# STM32_Schematic.net
KiCad netlist of a schematic drawn in Altium Designer
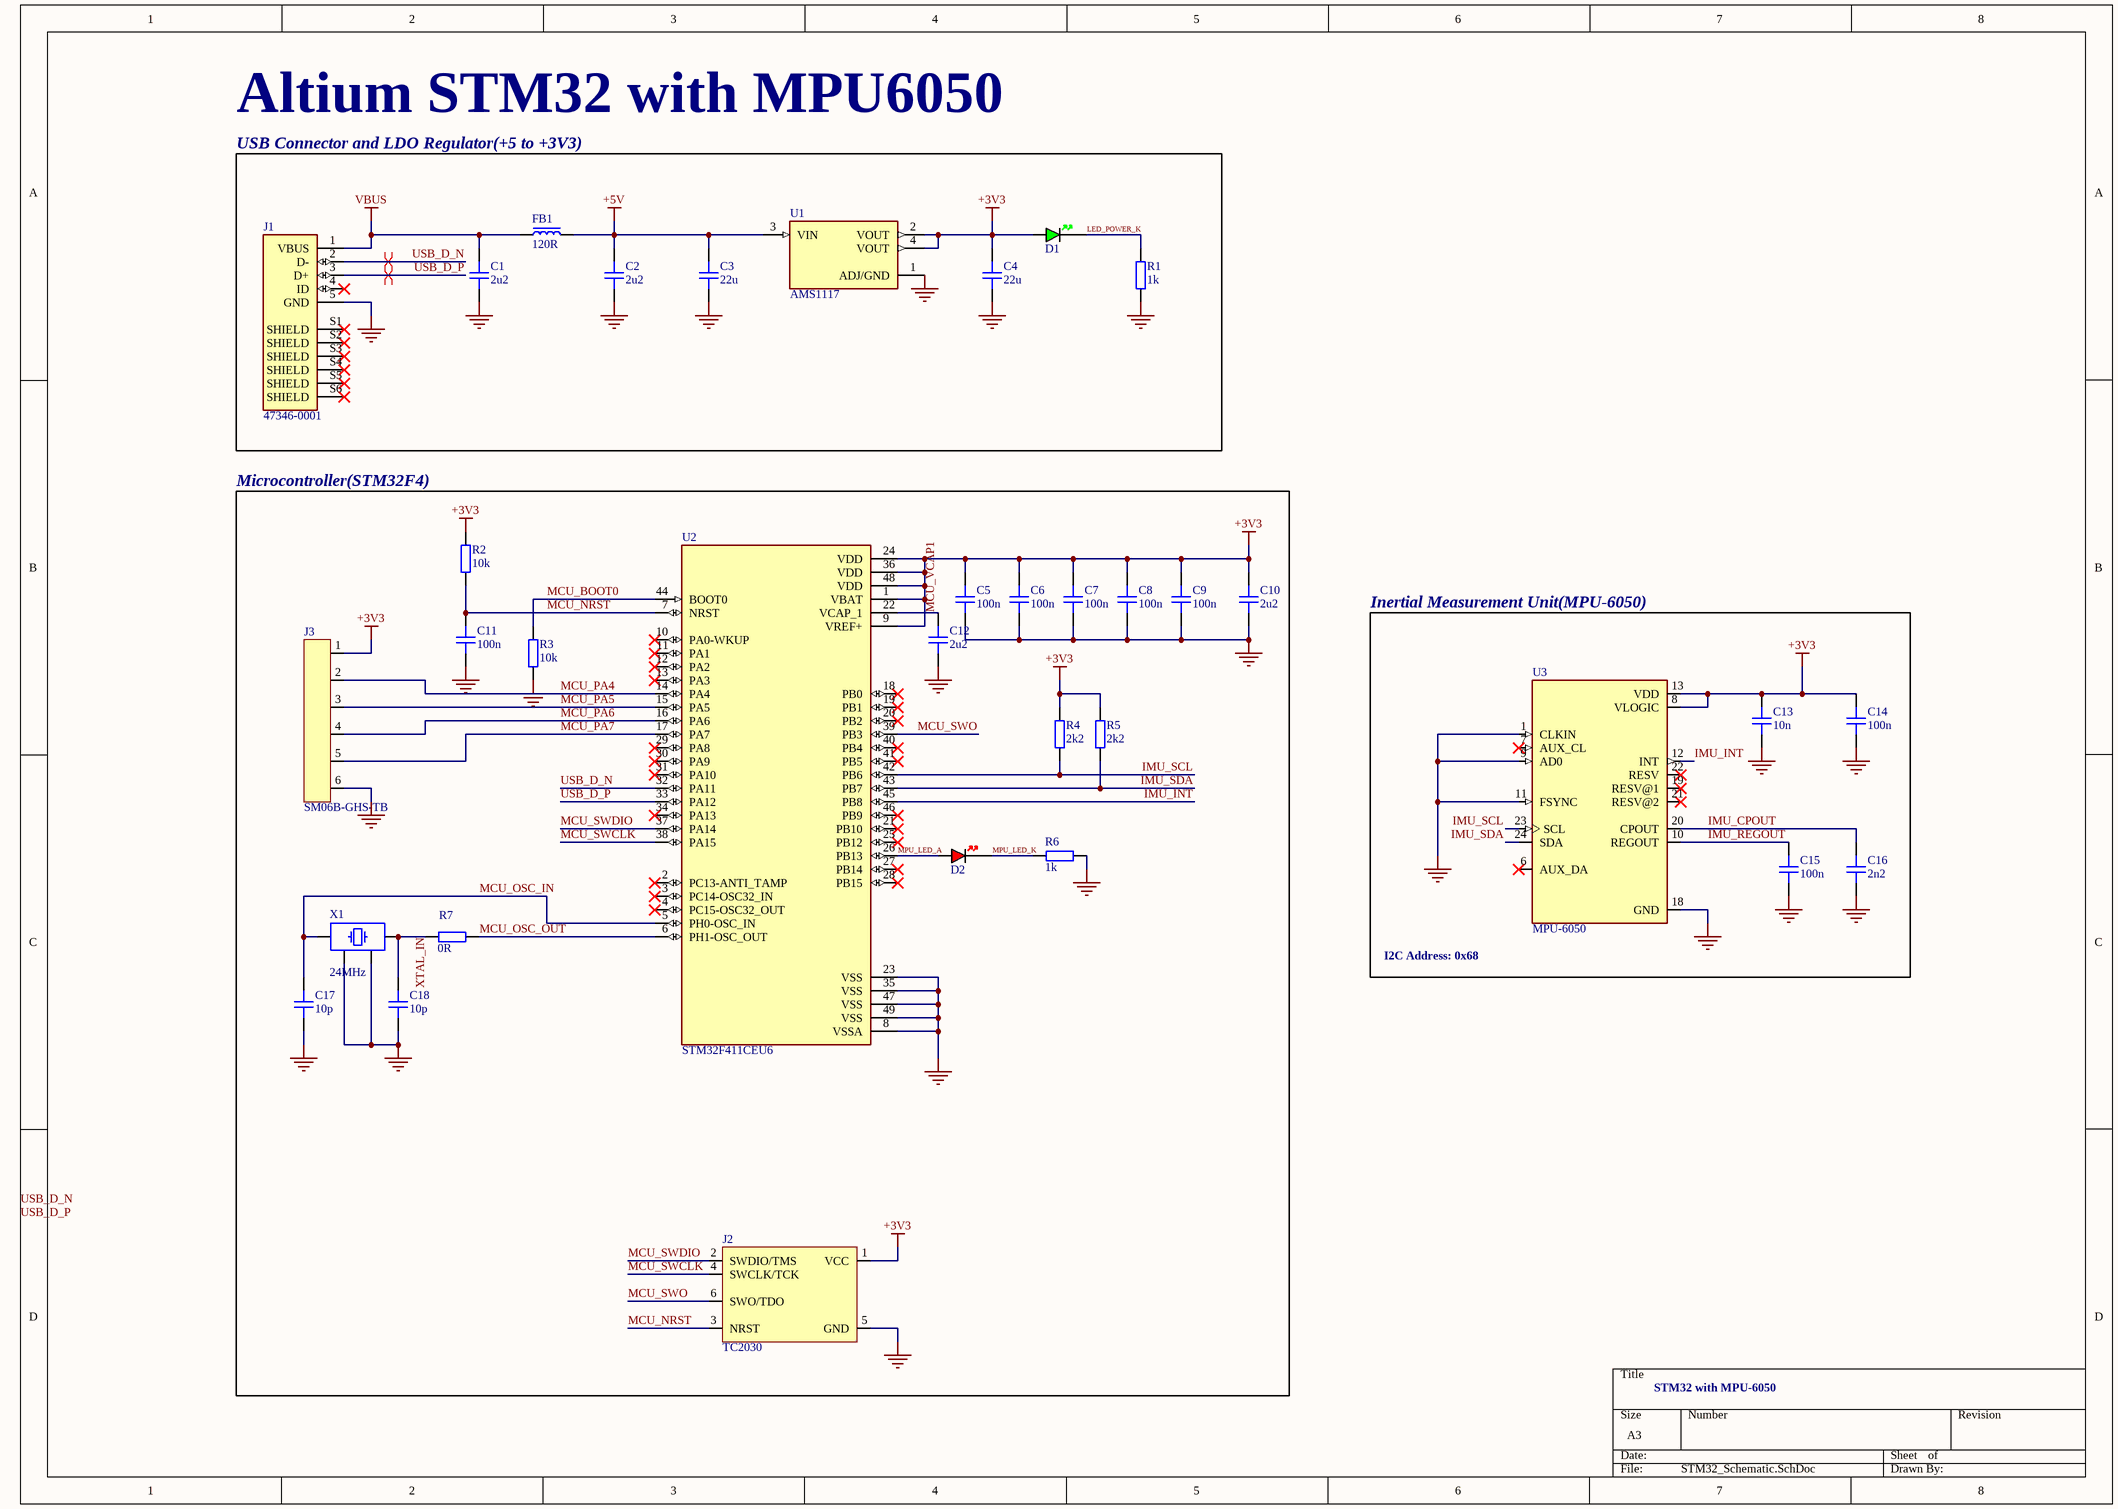
[diagram p0: STM32_Schematic.SchDoc]

(export (version "E")
  (design (tool "Eeschema 10.0.6"))
  (components
    (comp (ref "C1")
      (value "2u2")
      (footprint "CAP_0603")
      (description "Capacitor SMD 0603 16V")
      (libsource (lib "Schematic-Lib-PhilsLab") (part "CAP_0603_16V"))
    )
    (comp (ref "C2")
      (value "2u2")
      (footprint "CAP_0603")
      (description "Capacitor SMD 0603 16V")
      (libsource (lib "Schematic-Lib-PhilsLab") (part "CAP_0603_16V"))
    )
    (comp (ref "C3")
      (value "22u")
      (footprint "CAP_0805")
      (description "Capacitor SMD 0805 16V")
      (libsource (lib "Schematic-Lib-PhilsLab") (part "CAP_0805_16V"))
    )
    (comp (ref "C4")
      (value "22u")
      (footprint "CAP_0805")
      (description "Capacitor SMD 0805 16V")
      (libsource (lib "Schematic-Lib-PhilsLab") (part "CAP_0805_16V"))
    )
    (comp (ref "C5")
      (value "100n")
      (footprint "CAP_0402")
      (description "Capacitor SMD 0402 16V")
      (libsource (lib "Schematic-Lib-PhilsLab") (part "CAP_0402_16V"))
    )
    (comp (ref "C6")
      (value "100n")
      (footprint "CAP_0402")
      (description "Capacitor SMD 0402 16V")
      (libsource (lib "Schematic-Lib-PhilsLab") (part "CAP_0402_16V"))
    )
    (comp (ref "C7")
      (value "100n")
      (footprint "CAP_0402")
      (description "Capacitor SMD 0402 16V")
      (libsource (lib "Schematic-Lib-PhilsLab") (part "CAP_0402_16V"))
    )
    (comp (ref "C8")
      (value "100n")
      (footprint "CAP_0402")
      (description "Capacitor SMD 0402 16V")
      (libsource (lib "Schematic-Lib-PhilsLab") (part "CAP_0402_16V"))
    )
    (comp (ref "C9")
      (value "100n")
      (footprint "CAP_0402")
      (description "Capacitor SMD 0402 16V")
      (libsource (lib "Schematic-Lib-PhilsLab") (part "CAP_0402_16V"))
    )
    (comp (ref "C10")
      (value "2u2")
      (footprint "CAP_0603")
      (description "Capacitor SMD 0603 16V")
      (libsource (lib "Schematic-Lib-PhilsLab") (part "CAP_0603_16V"))
    )
    (comp (ref "C11")
      (value "100n")
      (footprint "CAP_0402")
      (description "Capacitor SMD 0402 16V")
      (libsource (lib "Schematic-Lib-PhilsLab") (part "CAP_0402_16V"))
    )
    (comp (ref "C12")
      (value "2u2")
      (footprint "CAP_0603")
      (description "Capacitor SMD 0603 16V")
      (libsource (lib "Schematic-Lib-PhilsLab") (part "CAP_0603_16V"))
    )
    (comp (ref "C13")
      (value "10n")
      (footprint "CAP_0402")
      (description "Capacitor SMD 0402 16V")
      (libsource (lib "Schematic-Lib-PhilsLab") (part "CAP_0402_16V"))
    )
    (comp (ref "C14")
      (value "100n")
      (footprint "CAP_0402")
      (description "Capacitor SMD 0402 16V")
      (libsource (lib "Schematic-Lib-PhilsLab") (part "CAP_0402_16V"))
    )
    (comp (ref "C15")
      (value "100n")
      (footprint "CAP_0402")
      (description "Capacitor SMD 0402 16V")
      (libsource (lib "Schematic-Lib-PhilsLab") (part "CAP_0402_16V"))
    )
    (comp (ref "C16")
      (value "2n2")
      (footprint "CAP_0402")
      (description "Capacitor SMD 0402 16V")
      (libsource (lib "Schematic-Lib-PhilsLab") (part "CAP_0402_16V"))
    )
    (comp (ref "C17")
      (value "10p")
      (footprint "CAP_0402")
      (description "Capacitor SMD 0402 16V")
      (libsource (lib "Schematic-Lib-PhilsLab") (part "CAP_0402_16V"))
    )
    (comp (ref "C18")
      (value "10p")
      (footprint "CAP_0402")
      (description "Capacitor SMD 0402 16V")
      (libsource (lib "Schematic-Lib-PhilsLab") (part "CAP_0402_16V"))
    )
    (comp (ref "D1")
      (value "GREEN")
      (footprint "LED_0402_GREEN")
      (description "LED 0402 GREEN SMD")
      (libsource (lib "Schematic-Lib-PhilsLab") (part "LED_0402_GREEN"))
    )
    (comp (ref "D2")
      (value "RED")
      (footprint "LED_0402_RED")
      (description "LED 0402 RED SMD")
      (libsource (lib "Schematic-Lib-PhilsLab") (part "LED_0402_RED"))
    )
    (comp (ref "FB1")
      (value "120R")
      (footprint "FB_0603")
      (description "Ferrite Bead SMD 0603")
      (libsource (lib "Schematic-Lib-PhilsLab") (part "FB_0603"))
    )
    (comp (ref "J1")
      (value "47346-0001")
      (footprint "MOLEX_47346-0001")
      (description "USB - micro B USB 2.0 Receptacle Connector 5 Position Surface Mount, Right Angle")
      (fields (field (name "MF") "Molex"))
      (libsource (lib "47346-0001") (part "47346-0001"))
    )
    (comp (ref "J2")
      (value "TC2030")
      (footprint "TC2030-FP")
      (description "Tag-Connect No-Solder SWD Debug Connector DO NOT PLACE")
      (fields (field (name "MANUFACTURER") "Tag-Connect"))
      (libsource (lib "Schematic-Lib-PhilsLab") (part "TC2030"))
    )
    (comp (ref "J3")
      (value "SM06B-GHS-TB")
      (footprint "SM06B-GHS-TB")
      (description "Header Connector 6 Position 1.25MM Pitch SMD Horizontal JST GH")
      (fields (field (name "MANUFACTURER") "JST"))
      (libsource (lib "Schematic-Lib-PhilsLab") (part "SM06B-GHS-TB"))
    )
    (comp (ref "R1")
      (value "1k")
      (footprint "RES_0402")
      (description "Resistor SMD 0402")
      (libsource (lib "Schematic-Lib-PhilsLab") (part "RES_0402"))
    )
    (comp (ref "R2")
      (value "10k")
      (footprint "RES_0402")
      (description "Resistor SMD 0402")
      (libsource (lib "Schematic-Lib-PhilsLab") (part "RES_0402"))
    )
    (comp (ref "R3")
      (value "10k")
      (footprint "RES_0402")
      (description "Resistor SMD 0402")
      (libsource (lib "Schematic-Lib-PhilsLab") (part "RES_0402"))
    )
    (comp (ref "R4")
      (value "2k2")
      (footprint "RES_0402")
      (description "Resistor SMD 0402")
      (libsource (lib "Schematic-Lib-PhilsLab") (part "RES_0402"))
    )
    (comp (ref "R5")
      (value "2k2")
      (footprint "RES_0402")
      (description "Resistor SMD 0402")
      (libsource (lib "Schematic-Lib-PhilsLab") (part "RES_0402"))
    )
    (comp (ref "R6")
      (value "1k")
      (footprint "RES_0402")
      (description "Resistor SMD 0402")
      (libsource (lib "Schematic-Lib-PhilsLab") (part "RES_0402"))
    )
    (comp (ref "R7")
      (value "0R")
      (footprint "RES_0402")
      (description "Resistor SMD 0402")
      (libsource (lib "Schematic-Lib-PhilsLab") (part "RES_0402"))
    )
    (comp (ref "U1")
      (value "AMS1117")
      (footprint "SOT229P700X180-4N")
      (description "1A LOW DROPOUT VOLTAGE REGULATOR SOT-223")
      (fields (field (name "MF") "Advanced Monolithic Systems"))
      (libsource (lib "AMS1117") (part "AMS1117"))
    )
    (comp (ref "U2")
      (value "STM32F411CEU6")
      (footprint "QFN50P700X700X60-49N:QFN50P700X700X60-49N")
      (libsource (lib "STM32F411CEU6") (part "STM32F411CEU6"))
    )
    (comp (ref "U3")
      (value "MPU-6050")
      (footprint "QFN50P400X400X95-24N")
      (description "MPU-6050 series Accelerometer, Gyroscope, 3 Axis Sensor Evaluation Board")
      (fields (field (name "MF") "TDK InvenSense"))
      (libsource (lib "MPU-6050") (part "MPU-6050"))
    )
    (comp (ref "X1")
      (value "24MHz")
      (footprint "XTAL_3225")
      (description "Crystal SMD 24MHz 10PPM 7pF 3225")
      (fields
        (field (name "MANUFACTURER") "Epson")
        (field (name "MANUFACTURER PART NUMBER") "TSX-3225 24.0000MF15X-AC")
      )
      (libsource (lib "Schematic-Lib-PhilsLab") (part "TSX-3225_24.0000MF15X-AC"))
    )
  )
  (nets
    (net (code "1") (name "+3V3") (class "Default")
      (node (ref "C10") (pin "1") (pinfunction "1_1") (pintype "passive"))
      (node (ref "C13") (pin "1") (pinfunction "1_1") (pintype "passive"))
      (node (ref "C14") (pin "1") (pinfunction "1_1") (pintype "passive"))
      (node (ref "C4") (pin "2") (pinfunction "2_2") (pintype "passive"))
      (node (ref "C5") (pin "2") (pinfunction "2_2") (pintype "passive"))
      (node (ref "C6") (pin "2") (pinfunction "2_2") (pintype "passive"))
      (node (ref "C7") (pin "2") (pinfunction "2_2") (pintype "passive"))
      (node (ref "C8") (pin "2") (pinfunction "2_2") (pintype "passive"))
      (node (ref "C9") (pin "1") (pinfunction "1_1") (pintype "passive"))
      (node (ref "D1") (pin "A") (pinfunction "A_A") (pintype "passive"))
      (node (ref "J2") (pin "1") (pinfunction "VCC_1") (pintype "passive"))
      (node (ref "J3") (pin "1") (pinfunction "1_1") (pintype "passive"))
      (node (ref "R2") (pin "2") (pinfunction "2_2") (pintype "passive"))
      (node (ref "R4") (pin "2") (pinfunction "2_2") (pintype "passive"))
      (node (ref "R5") (pin "2") (pinfunction "2_2") (pintype "passive"))
      (node (ref "U1") (pin "2") (pinfunction "VOUT_2") (pintype "output"))
      (node (ref "U1") (pin "4") (pinfunction "VOUT_4") (pintype "output"))
      (node (ref "U2") (pin "1") (pinfunction "VBAT_1") (pintype "power_in"))
      (node (ref "U2") (pin "24") (pinfunction "VDD_24") (pintype "power_in"))
      (node (ref "U2") (pin "36") (pinfunction "VDD_36") (pintype "power_in"))
      (node (ref "U2") (pin "48") (pinfunction "VDD_48") (pintype "power_in"))
      (node (ref "U2") (pin "9") (pinfunction "VREF+_9") (pintype "power_in"))
      (node (ref "U3") (pin "13") (pinfunction "VDD_13") (pintype "power_in"))
      (node (ref "U3") (pin "8") (pinfunction "VLOGIC_8") (pintype "power_in"))
    )
    (net (code "2") (name "+5V") (class "Default")
      (node (ref "C2") (pin "2") (pinfunction "2_2") (pintype "passive"))
      (node (ref "C3") (pin "2") (pinfunction "2_2") (pintype "passive"))
      (node (ref "FB1") (pin "2") (pinfunction "2_2") (pintype "passive"))
      (node (ref "U1") (pin "3") (pinfunction "VIN_3") (pintype "input"))
    )
    (net (code "3") (name "/IMU_CPOUT") (class "Default")
      (node (ref "C16") (pin "1") (pinfunction "1_1") (pintype "passive"))
      (node (ref "U3") (pin "20") (pinfunction "CPOUT_20") (pintype "passive"))
    )
    (net (code "4") (name "/IMU_INT") (class "Default")
      (node (ref "U2") (pin "45") (pinfunction "PB8_45") (pintype "bidirectional"))
      (node (ref "U3") (pin "12") (pinfunction "INT_12") (pintype "output"))
    )
    (net (code "5") (name "/IMU_REGOUT") (class "Default")
      (node (ref "C15") (pin "1") (pinfunction "1_1") (pintype "passive"))
      (node (ref "U3") (pin "10") (pinfunction "REGOUT_10") (pintype "passive"))
    )
    (net (code "6") (name "/IMU_SCL") (class "Default")
      (node (ref "R4") (pin "1") (pinfunction "1_1") (pintype "passive"))
      (node (ref "U2") (pin "42") (pinfunction "PB6_42") (pintype "bidirectional"))
      (node (ref "U3") (pin "23") (pinfunction "SCL_23") (pintype "input"))
    )
    (net (code "7") (name "/IMU_SDA") (class "Default")
      (node (ref "R5") (pin "1") (pinfunction "1_1") (pintype "passive"))
      (node (ref "U2") (pin "43") (pinfunction "PB7_43") (pintype "bidirectional"))
      (node (ref "U3") (pin "24") (pinfunction "SDA_24") (pintype "bidirectional"))
    )
    (net (code "8") (name "/LED_POWER_K") (class "Default")
      (node (ref "D1") (pin "K") (pinfunction "K_K") (pintype "passive"))
      (node (ref "R1") (pin "2") (pinfunction "2_2") (pintype "passive"))
    )
    (net (code "9") (name "/MCU_BOOT0") (class "Default")
      (node (ref "R3") (pin "2") (pinfunction "2_2") (pintype "passive"))
      (node (ref "U2") (pin "44") (pinfunction "BOOT0_44") (pintype "input"))
    )
    (net (code "10") (name "/MCU_NRST") (class "Default")
      (node (ref "C11") (pin "2") (pinfunction "2_2") (pintype "passive"))
      (node (ref "J2") (pin "3") (pinfunction "NRST_3") (pintype "passive"))
      (node (ref "R2") (pin "1") (pinfunction "1_1") (pintype "passive"))
      (node (ref "U2") (pin "7") (pinfunction "NRST_7") (pintype "bidirectional"))
    )
    (net (code "11") (name "/MCU_OSC_IN") (class "Default")
      (node (ref "C17") (pin "2") (pinfunction "2_2") (pintype "passive"))
      (node (ref "U2") (pin "5") (pinfunction "PH0-OSC_IN_5") (pintype "bidirectional"))
      (node (ref "X1") (pin "1") (pinfunction "1_1") (pintype "passive"))
    )
    (net (code "12") (name "/MCU_OSC_OUT") (class "Default")
      (node (ref "R7") (pin "2") (pinfunction "2_2") (pintype "passive"))
      (node (ref "U2") (pin "6") (pinfunction "PH1-OSC_OUT_6") (pintype "bidirectional"))
    )
    (net (code "13") (name "/MCU_PA4") (class "Default")
      (node (ref "J3") (pin "2") (pinfunction "2_2") (pintype "passive"))
      (node (ref "U2") (pin "14") (pinfunction "PA4_14") (pintype "bidirectional"))
    )
    (net (code "14") (name "/MCU_PA5") (class "Default")
      (node (ref "J3") (pin "3") (pinfunction "3_3") (pintype "passive"))
      (node (ref "U2") (pin "15") (pinfunction "PA5_15") (pintype "bidirectional"))
    )
    (net (code "15") (name "/MCU_PA6") (class "Default")
      (node (ref "J3") (pin "4") (pinfunction "4_4") (pintype "passive"))
      (node (ref "U2") (pin "16") (pinfunction "PA6_16") (pintype "bidirectional"))
    )
    (net (code "16") (name "/MCU_PA7") (class "Default")
      (node (ref "J3") (pin "5") (pinfunction "5_5") (pintype "passive"))
      (node (ref "U2") (pin "17") (pinfunction "PA7_17") (pintype "bidirectional"))
    )
    (net (code "17") (name "/MCU_SWCLK") (class "Default")
      (node (ref "J2") (pin "4") (pinfunction "SWCLK/TCK_4") (pintype "passive"))
      (node (ref "U2") (pin "38") (pinfunction "PA15_38") (pintype "bidirectional"))
    )
    (net (code "18") (name "/MCU_SWDIO") (class "Default")
      (node (ref "J2") (pin "2") (pinfunction "SWDIO/TMS_2") (pintype "passive"))
      (node (ref "U2") (pin "37") (pinfunction "PA14_37") (pintype "bidirectional"))
    )
    (net (code "19") (name "/MCU_SWO") (class "Default")
      (node (ref "J2") (pin "6") (pinfunction "SWO/TDO_6") (pintype "passive"))
      (node (ref "U2") (pin "39") (pinfunction "PB3_39") (pintype "bidirectional"))
    )
    (net (code "20") (name "/MCU_VCAP1") (class "Default")
      (node (ref "C12") (pin "1") (pinfunction "1_1") (pintype "passive"))
      (node (ref "U2") (pin "22") (pinfunction "VCAP_1_22") (pintype "power_in"))
    )
    (net (code "21") (name "/MPU_LED_A") (class "Default")
      (node (ref "D2") (pin "A") (pinfunction "A_A") (pintype "passive"))
      (node (ref "U2") (pin "26") (pinfunction "PB13_26") (pintype "bidirectional"))
    )
    (net (code "22") (name "/MPU_LED_K") (class "Default")
      (node (ref "D2") (pin "K") (pinfunction "K_K") (pintype "passive"))
      (node (ref "R6") (pin "1") (pinfunction "1_1") (pintype "passive"))
    )
    (net (code "23") (name "/USB_D_N") (class "Default")
      (node (ref "J1") (pin "2") (pinfunction "D-_2") (pintype "bidirectional"))
      (node (ref "U2") (pin "32") (pinfunction "PA11_32") (pintype "bidirectional"))
    )
    (net (code "24") (name "/USB_D_P") (class "Default")
      (node (ref "J1") (pin "3") (pinfunction "D+_3") (pintype "bidirectional"))
      (node (ref "U2") (pin "33") (pinfunction "PA12_33") (pintype "bidirectional"))
    )
    (net (code "25") (name "/XTAL_IN") (class "Default")
      (node (ref "C18") (pin "2") (pinfunction "2_2") (pintype "passive"))
      (node (ref "R7") (pin "1") (pinfunction "1_1") (pintype "passive"))
      (node (ref "X1") (pin "3") (pinfunction "3_3") (pintype "passive"))
    )
    (net (code "26") (name "GND") (class "Default")
      (node (ref "C1") (pin "1") (pinfunction "1_1") (pintype "passive"))
      (node (ref "C10") (pin "2") (pinfunction "2_2") (pintype "passive"))
      (node (ref "C11") (pin "1") (pinfunction "1_1") (pintype "passive"))
      (node (ref "C12") (pin "2") (pinfunction "2_2") (pintype "passive"))
      (node (ref "C13") (pin "2") (pinfunction "2_2") (pintype "passive"))
      (node (ref "C14") (pin "2") (pinfunction "2_2") (pintype "passive"))
      (node (ref "C15") (pin "2") (pinfunction "2_2") (pintype "passive"))
      (node (ref "C16") (pin "2") (pinfunction "2_2") (pintype "passive"))
      (node (ref "C17") (pin "1") (pinfunction "1_1") (pintype "passive"))
      (node (ref "C18") (pin "1") (pinfunction "1_1") (pintype "passive"))
      (node (ref "C2") (pin "1") (pinfunction "1_1") (pintype "passive"))
      (node (ref "C3") (pin "1") (pinfunction "1_1") (pintype "passive"))
      (node (ref "C4") (pin "1") (pinfunction "1_1") (pintype "passive"))
      (node (ref "C5") (pin "1") (pinfunction "1_1") (pintype "passive"))
      (node (ref "C6") (pin "1") (pinfunction "1_1") (pintype "passive"))
      (node (ref "C7") (pin "1") (pinfunction "1_1") (pintype "passive"))
      (node (ref "C8") (pin "1") (pinfunction "1_1") (pintype "passive"))
      (node (ref "C9") (pin "2") (pinfunction "2_2") (pintype "passive"))
      (node (ref "J1") (pin "5") (pinfunction "GND_5") (pintype "power_in"))
      (node (ref "J2") (pin "5") (pinfunction "GND_5") (pintype "passive"))
      (node (ref "J3") (pin "6") (pinfunction "6_6") (pintype "passive"))
      (node (ref "R1") (pin "1") (pinfunction "1_1") (pintype "passive"))
      (node (ref "R3") (pin "1") (pinfunction "1_1") (pintype "passive"))
      (node (ref "R6") (pin "2") (pinfunction "2_2") (pintype "passive"))
      (node (ref "U1") (pin "1") (pinfunction "ADJ/GND_1") (pintype "power_in"))
      (node (ref "U2") (pin "23") (pinfunction "VSS_23") (pintype "power_in"))
      (node (ref "U2") (pin "35") (pinfunction "VSS_35") (pintype "power_in"))
      (node (ref "U2") (pin "47") (pinfunction "VSS_47") (pintype "power_in"))
      (node (ref "U2") (pin "49") (pinfunction "VSS_49") (pintype "power_in"))
      (node (ref "U2") (pin "8") (pinfunction "VSSA_8") (pintype "power_in"))
      (node (ref "U3") (pin "1") (pinfunction "CLKIN_1") (pintype "input"))
      (node (ref "U3") (pin "11") (pinfunction "FSYNC_11") (pintype "input"))
      (node (ref "U3") (pin "18") (pinfunction "GND_18") (pintype "power_in"))
      (node (ref "U3") (pin "9") (pinfunction "AD0_9") (pintype "input"))
      (node (ref "X1") (pin "2") (pinfunction "2_2") (pintype "passive"))
      (node (ref "X1") (pin "4") (pinfunction "4_4") (pintype "passive"))
    )
    (net (code "27") (name "VBUS") (class "Default")
      (node (ref "C1") (pin "2") (pinfunction "2_2") (pintype "passive"))
      (node (ref "FB1") (pin "1") (pinfunction "1_1") (pintype "passive"))
      (node (ref "J1") (pin "1") (pinfunction "VBUS_1") (pintype "power_in"))
    )
    (net (code "28") (name "unconnected-(J1-ID-Pad4)") (class "Default")
      (node (ref "J1") (pin "4") (pinfunction "ID_4") (pintype "bidirectional+no_connect"))
    )
    (net (code "29") (name "unconnected-(J1-SHIELD-PadS1)") (class "Default")
      (node (ref "J1") (pin "S1") (pinfunction "SHIELD_S1") (pintype "passive+no_connect"))
    )
    (net (code "30") (name "unconnected-(J1-SHIELD-PadS2)") (class "Default")
      (node (ref "J1") (pin "S2") (pinfunction "SHIELD_S2") (pintype "passive+no_connect"))
    )
    (net (code "31") (name "unconnected-(J1-SHIELD-PadS3)") (class "Default")
      (node (ref "J1") (pin "S3") (pinfunction "SHIELD_S3") (pintype "passive+no_connect"))
    )
    (net (code "32") (name "unconnected-(J1-SHIELD-PadS4)") (class "Default")
      (node (ref "J1") (pin "S4") (pinfunction "SHIELD_S4") (pintype "passive+no_connect"))
    )
    (net (code "33") (name "unconnected-(J1-SHIELD-PadS5)") (class "Default")
      (node (ref "J1") (pin "S5") (pinfunction "SHIELD_S5") (pintype "passive+no_connect"))
    )
    (net (code "34") (name "unconnected-(J1-SHIELD-PadS6)") (class "Default")
      (node (ref "J1") (pin "S6") (pinfunction "SHIELD_S6") (pintype "passive+no_connect"))
    )
    (net (code "35") (name "unconnected-(U2-PA0-WKUP-Pad10)") (class "Default")
      (node (ref "U2") (pin "10") (pinfunction "PA0-WKUP_10") (pintype "bidirectional+no_connect"))
    )
    (net (code "36") (name "unconnected-(U2-PA1-Pad11)") (class "Default")
      (node (ref "U2") (pin "11") (pinfunction "PA1_11") (pintype "bidirectional+no_connect"))
    )
    (net (code "37") (name "unconnected-(U2-PA2-Pad12)") (class "Default")
      (node (ref "U2") (pin "12") (pinfunction "PA2_12") (pintype "bidirectional+no_connect"))
    )
    (net (code "38") (name "unconnected-(U2-PA3-Pad13)") (class "Default")
      (node (ref "U2") (pin "13") (pinfunction "PA3_13") (pintype "bidirectional+no_connect"))
    )
    (net (code "39") (name "unconnected-(U2-PA8-Pad29)") (class "Default")
      (node (ref "U2") (pin "29") (pinfunction "PA8_29") (pintype "bidirectional+no_connect"))
    )
    (net (code "40") (name "unconnected-(U2-PA9-Pad30)") (class "Default")
      (node (ref "U2") (pin "30") (pinfunction "PA9_30") (pintype "bidirectional+no_connect"))
    )
    (net (code "41") (name "unconnected-(U2-PA10-Pad31)") (class "Default")
      (node (ref "U2") (pin "31") (pinfunction "PA10_31") (pintype "bidirectional+no_connect"))
    )
    (net (code "42") (name "unconnected-(U2-PA13-Pad34)") (class "Default")
      (node (ref "U2") (pin "34") (pinfunction "PA13_34") (pintype "bidirectional+no_connect"))
    )
    (net (code "43") (name "unconnected-(U2-PB0-Pad18)") (class "Default")
      (node (ref "U2") (pin "18") (pinfunction "PB0_18") (pintype "bidirectional+no_connect"))
    )
    (net (code "44") (name "unconnected-(U2-PB1-Pad19)") (class "Default")
      (node (ref "U2") (pin "19") (pinfunction "PB1_19") (pintype "bidirectional+no_connect"))
    )
    (net (code "45") (name "unconnected-(U2-PB2-Pad20)") (class "Default")
      (node (ref "U2") (pin "20") (pinfunction "PB2_20") (pintype "bidirectional+no_connect"))
    )
    (net (code "46") (name "unconnected-(U2-PB4-Pad40)") (class "Default")
      (node (ref "U2") (pin "40") (pinfunction "PB4_40") (pintype "bidirectional+no_connect"))
    )
    (net (code "47") (name "unconnected-(U2-PB5-Pad41)") (class "Default")
      (node (ref "U2") (pin "41") (pinfunction "PB5_41") (pintype "bidirectional+no_connect"))
    )
    (net (code "48") (name "unconnected-(U2-PB9-Pad46)") (class "Default")
      (node (ref "U2") (pin "46") (pinfunction "PB9_46") (pintype "bidirectional+no_connect"))
    )
    (net (code "49") (name "unconnected-(U2-PB10-Pad21)") (class "Default")
      (node (ref "U2") (pin "21") (pinfunction "PB10_21") (pintype "bidirectional+no_connect"))
    )
    (net (code "50") (name "unconnected-(U2-PB12-Pad25)") (class "Default")
      (node (ref "U2") (pin "25") (pinfunction "PB12_25") (pintype "bidirectional+no_connect"))
    )
    (net (code "51") (name "unconnected-(U2-PB14-Pad27)") (class "Default")
      (node (ref "U2") (pin "27") (pinfunction "PB14_27") (pintype "bidirectional+no_connect"))
    )
    (net (code "52") (name "unconnected-(U2-PB15-Pad28)") (class "Default")
      (node (ref "U2") (pin "28") (pinfunction "PB15_28") (pintype "bidirectional+no_connect"))
    )
    (net (code "53") (name "unconnected-(U2-PC13-ANTI_TAMP-Pad2)") (class "Default")
      (node (ref "U2") (pin "2") (pinfunction "PC13-ANTI_TAMP_2") (pintype "bidirectional+no_connect"))
    )
    (net (code "54") (name "unconnected-(U2-PC14-OSC32_IN-Pad3)") (class "Default")
      (node (ref "U2") (pin "3") (pinfunction "PC14-OSC32_IN_3") (pintype "bidirectional+no_connect"))
    )
    (net (code "55") (name "unconnected-(U2-PC15-OSC32_OUT-Pad4)") (class "Default")
      (node (ref "U2") (pin "4") (pinfunction "PC15-OSC32_OUT_4") (pintype "bidirectional+no_connect"))
    )
    (net (code "56") (name "unconnected-(U3-AUX_CL-Pad7)") (class "Default")
      (node (ref "U3") (pin "7") (pinfunction "AUX_CL_7") (pintype "input+no_connect"))
    )
    (net (code "57") (name "unconnected-(U3-AUX_DA-Pad6)") (class "Default")
      (node (ref "U3") (pin "6") (pinfunction "AUX_DA_6") (pintype "bidirectional+no_connect"))
    )
    (net (code "58") (name "unconnected-(U3-RESV-Pad22)") (class "Default")
      (node (ref "U3") (pin "22") (pinfunction "RESV_22") (pintype "passive+no_connect"))
    )
    (net (code "59") (name "unconnected-(U3-RESV@1-Pad19)") (class "Default")
      (node (ref "U3") (pin "19") (pinfunction "RESV@1_19") (pintype "passive+no_connect"))
    )
    (net (code "60") (name "unconnected-(U3-RESV@2-Pad21)") (class "Default")
      (node (ref "U3") (pin "21") (pinfunction "RESV@2_21") (pintype "passive+no_connect"))
    )
  )
)
